# bqZUM_Autoreset.net
KiCad netlist of a schematic drawn in Altium Designer
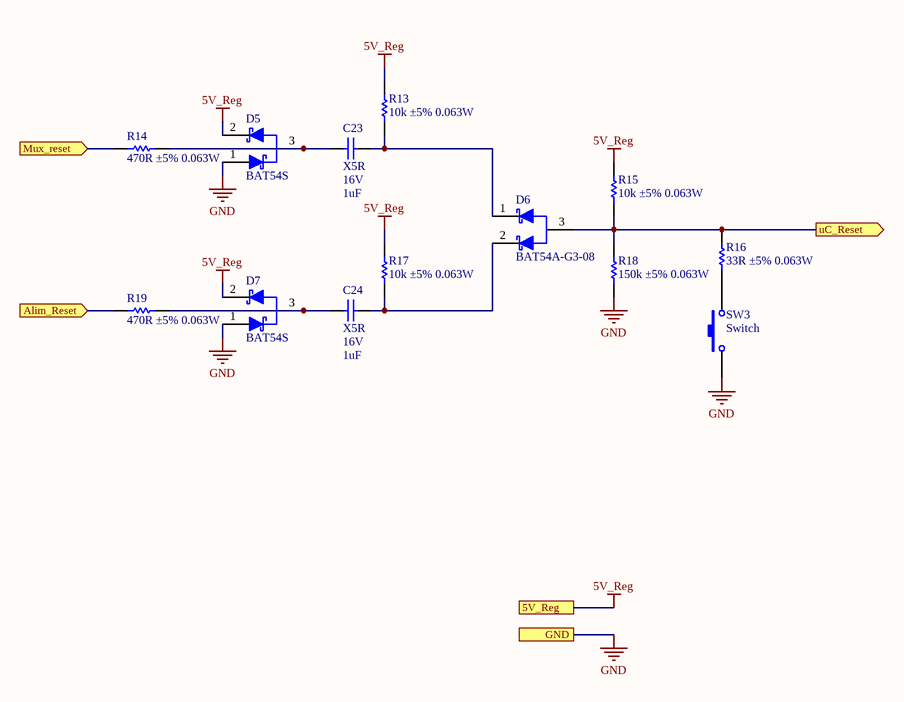
[diagram p0: bqZUM_Autoreset.SchDoc]

(export (version "E")
  (design (tool "Eeschema 10.0.6"))
  (components
    (comp (ref "C23")
      (value "Capacitor")
      (footprint "C0603")
      (fields
        (field (name "DIELECTRIC") "X5R")
        (field (name "VOLTAGE") "16V")
        (field (name "CAPACITANCE") "1uF")
        (field (name "PART NUMBER") "C0603_1uF_16V_±10%")
        (field (name "TOLERANCE") "±10%")
        (field (name "MANUFACTURER") "Kemet")
      )
      (libsource (lib "Pasives_Capacitor_SMD") (part "Capacitor"))
    )
    (comp (ref "C24")
      (value "Capacitor")
      (footprint "C0603")
      (fields
        (field (name "DIELECTRIC") "X5R")
        (field (name "VOLTAGE") "16V")
        (field (name "CAPACITANCE") "1uF")
        (field (name "PART NUMBER") "C0603_1uF_16V_±10%")
        (field (name "TOLERANCE") "±10%")
        (field (name "MANUFACTURER") "Kemet")
      )
      (libsource (lib "Pasives_Capacitor_SMD") (part "Capacitor"))
    )
    (comp (ref "D5")
      (value "BAT54S")
      (footprint "SOT23-3")
      (description "Dual Schottky Diode")
      (fields (field (name "MANUFACTURER") "NXP"))
      (libsource (lib "Semiconductors_Diodes") (part "Dual Schottky"))
    )
    (comp (ref "D6")
      (value "BAT54A-G3-08")
      (footprint "SOT23-3")
      (description "Dual Schottky Diode Common Anode")
      (fields (field (name "PART NUMBER") "BAT54A") (field (name "MANUFACTURER") "Vishay"))
      (libsource (lib "Semiconductors_Diodes") (part "Dual_Diode_Schottky_A"))
    )
    (comp (ref "D7")
      (value "BAT54S")
      (footprint "SOT23-3")
      (description "Dual Schottky Diode")
      (fields (field (name "MANUFACTURER") "NXP"))
      (libsource (lib "Semiconductors_Diodes") (part "Dual Schottky"))
    )
    (comp (ref "R13")
      (value "10k ±5% 0.063W")
      (footprint "R0402")
      (description "Resistor")
      (fields (field (name "TOLERANCE") "±5%") (field (name "POWER") "0.063W"))
      (libsource (lib "Pasives_Resistor_SMD") (part "Resistor"))
    )
    (comp (ref "R14")
      (value "470R ±5% 0.063W")
      (footprint "R0402")
      (description "Resistor")
      (fields (field (name "TOLERANCE") "±5%") (field (name "POWER") "0.063W"))
      (libsource (lib "Pasives_Resistor_SMD") (part "Resistor"))
    )
    (comp (ref "R15")
      (value "10k ±5% 0.063W")
      (footprint "R0402")
      (description "Resistor")
      (fields (field (name "TOLERANCE") "±5%") (field (name "POWER") "0.063W"))
      (libsource (lib "Pasives_Resistor_SMD") (part "Resistor"))
    )
    (comp (ref "R16")
      (value "33R ±5% 0.063W")
      (footprint "R0402")
      (description "Resistor")
      (fields (field (name "TOLERANCE") "±5%") (field (name "POWER") "0.063W"))
      (libsource (lib "Pasives_Resistor_SMD") (part "Resistor"))
    )
    (comp (ref "R17")
      (value "10k ±5% 0.063W")
      (footprint "R0402")
      (description "Resistor")
      (fields (field (name "TOLERANCE") "±5%") (field (name "POWER") "0.063W"))
      (libsource (lib "Pasives_Resistor_SMD") (part "Resistor"))
    )
    (comp (ref "R18")
      (value "150k ±5% 0.063W")
      (footprint "R0402")
      (description "Resistor")
      (fields (field (name "TOLERANCE") "±5%") (field (name "POWER") "0.063W"))
      (libsource (lib "Pasives_Resistor_SMD") (part "Resistor"))
    )
    (comp (ref "R19")
      (value "470R ±5% 0.063W")
      (footprint "R0402")
      (description "Resistor")
      (fields (field (name "TOLERANCE") "±5%") (field (name "POWER") "0.063W"))
      (libsource (lib "Pasives_Resistor_SMD") (part "Resistor"))
    )
    (comp (ref "SW3")
      (value "Switch")
      (footprint "SW_Vert_THT_7.5x6x6.5")
      (description "Micro miniature pushbutton surface Switch")
      (fields (field (name "PART NUMBER") "SW Vertical THT") (field (name "MANUFACTURER") "C&K Components"))
      (libsource (lib "Electromechanical") (part "Switch"))
    )
  )
  (nets
    (net (code "1") (name "/Alim_Reset") (class "Default")
      (node (ref "R19") (pin "1") (pinfunction "1_1") (pintype "passive"))
    )
    (net (code "2") (name "/Mux_reset") (class "Default")
      (node (ref "R14") (pin "1") (pinfunction "1_1") (pintype "passive"))
    )
    (net (code "3") (name "/uC_Reset") (class "Default")
      (node (ref "D6") (pin "3") (pinfunction "K_3") (pintype "passive"))
      (node (ref "R15") (pin "1") (pinfunction "1_1") (pintype "passive"))
      (node (ref "R16") (pin "2") (pinfunction "2_2") (pintype "passive"))
      (node (ref "R18") (pin "2") (pinfunction "2_2") (pintype "passive"))
    )
    (net (code "4") (name "5V_Reg") (class "Default")
      (node (ref "D5") (pin "2") (pinfunction "K2_2") (pintype "passive"))
      (node (ref "D7") (pin "2") (pinfunction "K2_2") (pintype "passive"))
      (node (ref "R13") (pin "2") (pinfunction "2_2") (pintype "passive"))
      (node (ref "R15") (pin "2") (pinfunction "2_2") (pintype "passive"))
      (node (ref "R17") (pin "2") (pinfunction "2_2") (pintype "passive"))
    )
    (net (code "5") (name "GND") (class "Default")
      (node (ref "D5") (pin "1") (pinfunction "A_1") (pintype "passive"))
      (node (ref "D7") (pin "1") (pinfunction "A_1") (pintype "passive"))
      (node (ref "R18") (pin "1") (pinfunction "1_1") (pintype "passive"))
      (node (ref "SW3") (pin "2") (pinfunction "2_2") (pintype "passive"))
    )
    (net (code "6") (name "Net-(D5-K1)") (class "Default")
      (node (ref "C23") (pin "1") (pinfunction "1_1") (pintype "passive"))
      (node (ref "D5") (pin "3") (pinfunction "K1_3") (pintype "passive"))
      (node (ref "R14") (pin "2") (pinfunction "2_2") (pintype "passive"))
    )
    (net (code "7") (name "Net-(D6-A1)") (class "Default")
      (node (ref "C23") (pin "2") (pinfunction "2_2") (pintype "passive"))
      (node (ref "D6") (pin "1") (pinfunction "A1_1") (pintype "passive"))
      (node (ref "R13") (pin "1") (pinfunction "1_1") (pintype "passive"))
    )
    (net (code "8") (name "Net-(D6-A2)") (class "Default")
      (node (ref "C24") (pin "2") (pinfunction "2_2") (pintype "passive"))
      (node (ref "D6") (pin "2") (pinfunction "A2_2") (pintype "passive"))
      (node (ref "R17") (pin "1") (pinfunction "1_1") (pintype "passive"))
    )
    (net (code "9") (name "Net-(D7-K1)") (class "Default")
      (node (ref "C24") (pin "1") (pinfunction "1_1") (pintype "passive"))
      (node (ref "D7") (pin "3") (pinfunction "K1_3") (pintype "passive"))
      (node (ref "R19") (pin "2") (pinfunction "2_2") (pintype "passive"))
    )
    (net (code "10") (name "Net-(R16-Pad1)") (class "Default")
      (node (ref "R16") (pin "1") (pinfunction "1_1") (pintype "passive"))
      (node (ref "SW3") (pin "1") (pinfunction "1_1") (pintype "passive"))
    )
  )
)
